# IR_module_V4.net
KiCad netlist of a schematic drawn in EAGLE
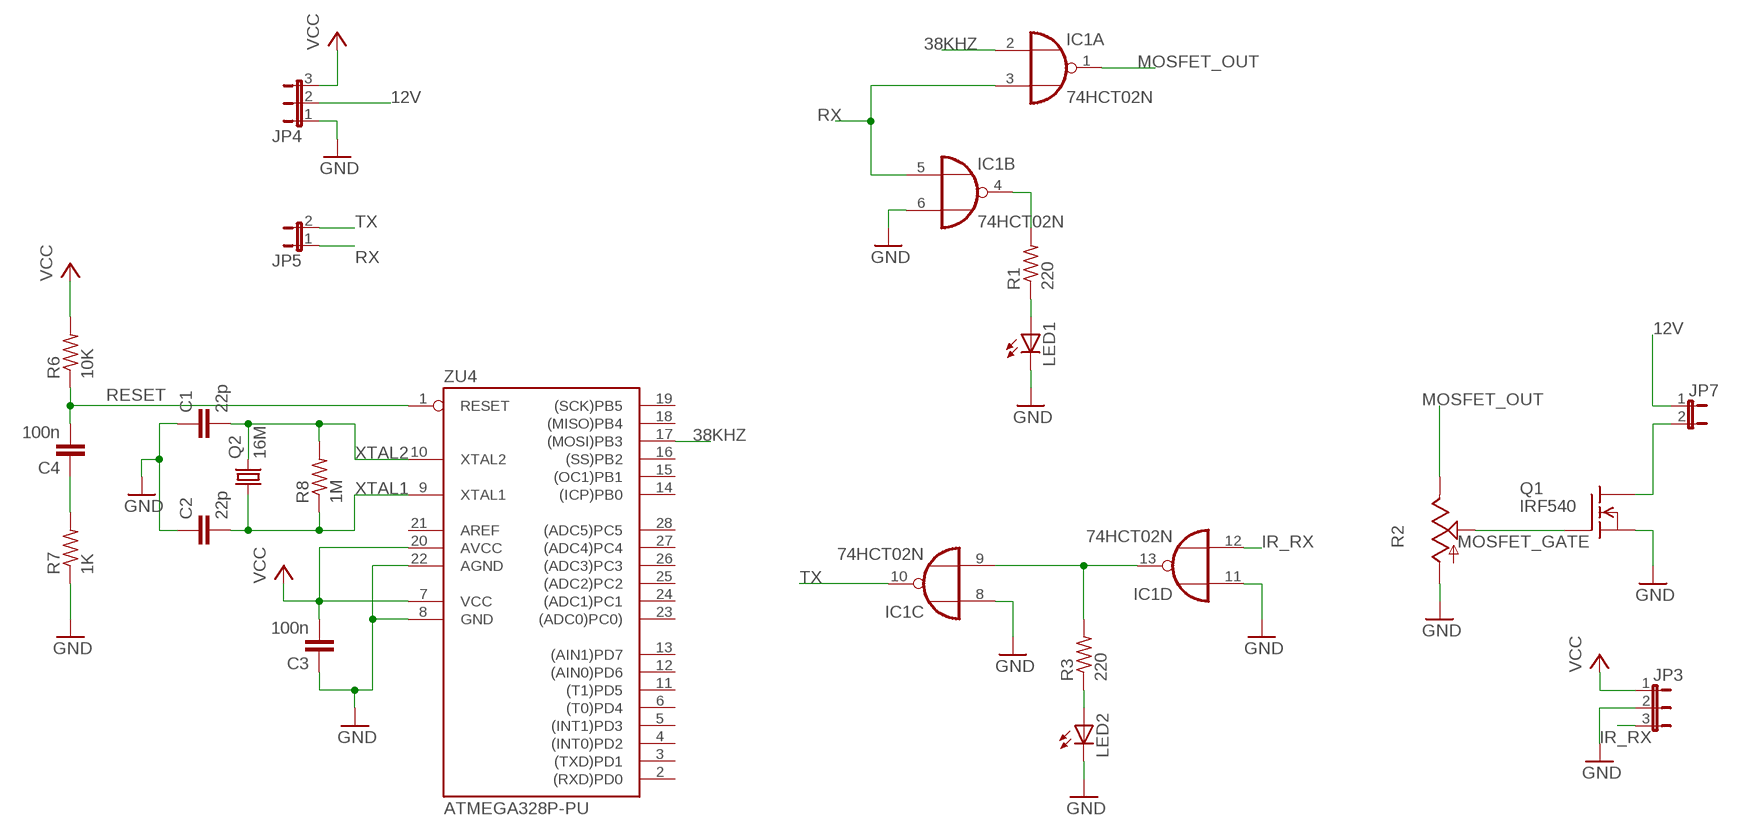
[diagram p0: schematic, sheet 1]

(export (version "E")
  (design (tool "Eeschema 10.0.6"))
  (components
    (comp (ref "C1")
      (value "22p")
      (footprint "eagle-import:CAP-PTH-SMALLEZ")
      (libsource (lib "eagle-import") (part "CAPEZ"))
    )
    (comp (ref "C2")
      (value "22p")
      (footprint "eagle-import:CAP-PTH-SMALLEZ")
      (libsource (lib "eagle-import") (part "CAPEZ"))
    )
    (comp (ref "C3")
      (value "100n")
      (footprint "eagle-import:CAP-PTH-SMALLEZ")
      (libsource (lib "eagle-import") (part "CAPEZ"))
    )
    (comp (ref "C4")
      (value "100n")
      (footprint "eagle-import:CAP-PTH-SMALLEZ")
      (libsource (lib "eagle-import") (part "CAPEZ"))
    )
    (comp (ref "IC1")
      (value "74HCT02N")
      (footprint "eagle-import:DIL14")
      (libsource (lib "eagle-import") (part "7402NHCT"))
    )
    (comp (ref "JP3")
      (value "JP2E")
      (footprint "eagle-import:JP2")
      (libsource (lib "eagle-import") (part "JP2E"))
    )
    (comp (ref "JP4")
      (value "JP2E")
      (footprint "eagle-import:JP2")
      (libsource (lib "eagle-import") (part "JP2E"))
    )
    (comp (ref "JP5")
      (value "JP1E")
      (footprint "eagle-import:JP1")
      (libsource (lib "eagle-import") (part "JP1E"))
    )
    (comp (ref "JP7")
      (value "JP1E")
      (footprint "eagle-import:JP1")
      (libsource (lib "eagle-import") (part "JP1E"))
    )
    (comp (ref "LED1")
      (value "LED5MM")
      (footprint "eagle-import:LED5MM")
      (libsource (lib "eagle-import") (part "LED5MM"))
    )
    (comp (ref "LED2")
      (value "LED5MM")
      (footprint "eagle-import:LED5MM")
      (libsource (lib "eagle-import") (part "LED5MM"))
    )
    (comp (ref "Q1")
      (value "IRF540")
      (footprint "eagle-import:TO220")
      (libsource (lib "eagle-import") (part "IRF540"))
    )
    (comp (ref "Q2")
      (value "16M")
      (footprint "eagle-import:HC49_S")
      (libsource (lib "eagle-import") (part "CRYSTALHC49S"))
    )
    (comp (ref "R1")
      (value "220")
      (footprint "eagle-import:0207_10")
      (libsource (lib "eagle-import") (part "R-US_0207/10"))
    )
    (comp (ref "R2")
      (value "TRIM_US-B25P")
      (footprint "eagle-import:B25P")
      (libsource (lib "eagle-import") (part "TRIM_US-B25P"))
    )
    (comp (ref "R3")
      (value "220")
      (footprint "eagle-import:0207_10")
      (libsource (lib "eagle-import") (part "R-US_0207/10"))
    )
    (comp (ref "R6")
      (value "10K")
      (footprint "eagle-import:0207_10")
      (libsource (lib "eagle-import") (part "R-US_0207/10"))
    )
    (comp (ref "R7")
      (value "1K")
      (footprint "eagle-import:0207_10")
      (libsource (lib "eagle-import") (part "R-US_0207/10"))
    )
    (comp (ref "R8")
      (value "1M")
      (footprint "eagle-import:0207_10")
      (libsource (lib "eagle-import") (part "R-US_0207/10"))
    )
    (comp (ref "ZU4")
      (value "ATMEGA328P-PU")
      (footprint "eagle-import:DIL28-3")
      (libsource (lib "eagle-import") (part "ATMEGA328P-PU"))
    )
  )
  (nets
    (net (code "1") (name "/12V") (class "Default")
      (node (ref "JP4") (pin "2") (pinfunction "2_2") (pintype "passive"))
      (node (ref "JP7") (pin "1") (pinfunction "1_1") (pintype "passive"))
    )
    (net (code "2") (name "/38KHZ") (class "Default")
      (node (ref "IC1") (pin "2") (pinfunction "I0_2") (pintype "input"))
      (node (ref "ZU4") (pin "17") (pinfunction "(MOSI)PB3_17") (pintype "bidirectional"))
    )
    (net (code "3") (name "/IR_RX") (class "Default")
      (node (ref "IC1") (pin "12") (pinfunction "I1_12") (pintype "input"))
      (node (ref "JP3") (pin "3") (pinfunction "3_3") (pintype "passive"))
    )
    (net (code "4") (name "/MOSFET_GATE") (class "Default")
      (node (ref "Q1") (pin "1") (pinfunction "G_1") (pintype "passive"))
      (node (ref "R2") (pin "S") (pinfunction "S_S") (pintype "passive"))
    )
    (net (code "5") (name "/MOSFET_OUT") (class "Default")
      (node (ref "IC1") (pin "1") (pinfunction "O_1") (pintype "output"))
      (node (ref "R2") (pin "E") (pinfunction "E_E") (pintype "passive"))
    )
    (net (code "6") (name "/RESET") (class "Default")
      (node (ref "C4") (pin "2") (pinfunction "2_2") (pintype "passive"))
      (node (ref "R6") (pin "1") (pinfunction "1_1") (pintype "passive"))
      (node (ref "ZU4") (pin "1") (pinfunction "RESET_1") (pintype "input"))
    )
    (net (code "7") (name "/RX") (class "Default")
      (node (ref "IC1") (pin "3") (pinfunction "I1_3") (pintype "input"))
      (node (ref "IC1") (pin "5") (pinfunction "I0_5") (pintype "input"))
      (node (ref "JP5") (pin "1") (pinfunction "1_1") (pintype "passive"))
    )
    (net (code "8") (name "/TX") (class "Default")
      (node (ref "IC1") (pin "10") (pinfunction "O_10") (pintype "output"))
      (node (ref "JP5") (pin "2") (pinfunction "2_2") (pintype "passive"))
    )
    (net (code "9") (name "/XTAL1") (class "Default")
      (node (ref "C2") (pin "2") (pinfunction "2_2") (pintype "passive"))
      (node (ref "Q2") (pin "1") (pinfunction "1_1") (pintype "passive"))
      (node (ref "R8") (pin "1") (pinfunction "1_1") (pintype "passive"))
      (node (ref "ZU4") (pin "9") (pinfunction "XTAL1_9") (pintype "bidirectional"))
    )
    (net (code "10") (name "/XTAL2") (class "Default")
      (node (ref "C1") (pin "2") (pinfunction "2_2") (pintype "passive"))
      (node (ref "Q2") (pin "2") (pinfunction "2_2") (pintype "passive"))
      (node (ref "R8") (pin "2") (pinfunction "2_2") (pintype "passive"))
      (node (ref "ZU4") (pin "10") (pinfunction "XTAL2_10") (pintype "bidirectional"))
    )
    (net (code "11") (name "GND") (class "Default")
      (node (ref "C1") (pin "1") (pinfunction "1_1") (pintype "passive"))
      (node (ref "C2") (pin "1") (pinfunction "1_1") (pintype "passive"))
      (node (ref "C3") (pin "1") (pinfunction "1_1") (pintype "passive"))
      (node (ref "IC1") (pin "11") (pinfunction "I0_11") (pintype "input"))
      (node (ref "IC1") (pin "6") (pinfunction "I1_6") (pintype "input"))
      (node (ref "IC1") (pin "8") (pinfunction "I0_8") (pintype "input"))
      (node (ref "JP3") (pin "2") (pinfunction "2_2") (pintype "passive"))
      (node (ref "JP4") (pin "1") (pinfunction "1_1") (pintype "passive"))
      (node (ref "LED1") (pin "K") (pinfunction "C_K") (pintype "passive"))
      (node (ref "LED2") (pin "K") (pinfunction "C_K") (pintype "passive"))
      (node (ref "Q1") (pin "3") (pinfunction "S_3") (pintype "passive"))
      (node (ref "R2") (pin "A") (pinfunction "A_A") (pintype "passive"))
      (node (ref "R7") (pin "1") (pinfunction "1_1") (pintype "passive"))
      (node (ref "ZU4") (pin "22") (pinfunction "AGND_22") (pintype "power_in"))
      (node (ref "ZU4") (pin "8") (pinfunction "GND_8") (pintype "power_in"))
    )
    (net (code "12") (name "Net-(C4-Pad1)") (class "Default")
      (node (ref "C4") (pin "1") (pinfunction "1_1") (pintype "passive"))
      (node (ref "R7") (pin "2") (pinfunction "2_2") (pintype "passive"))
    )
    (net (code "13") (name "Net-(IC1B-O)") (class "Default")
      (node (ref "IC1") (pin "4") (pinfunction "O_4") (pintype "output"))
      (node (ref "R1") (pin "2") (pinfunction "2_2") (pintype "passive"))
    )
    (net (code "14") (name "Net-(IC1C-I1)") (class "Default")
      (node (ref "IC1") (pin "13") (pinfunction "O_13") (pintype "output"))
      (node (ref "IC1") (pin "9") (pinfunction "I1_9") (pintype "input"))
      (node (ref "R3") (pin "2") (pinfunction "2_2") (pintype "passive"))
    )
    (net (code "15") (name "Net-(LED1-PadA)") (class "Default")
      (node (ref "LED1") (pin "A") (pinfunction "A_A") (pintype "passive"))
      (node (ref "R1") (pin "1") (pinfunction "1_1") (pintype "passive"))
    )
    (net (code "16") (name "Net-(LED2-PadA)") (class "Default")
      (node (ref "LED2") (pin "A") (pinfunction "A_A") (pintype "passive"))
      (node (ref "R3") (pin "1") (pinfunction "1_1") (pintype "passive"))
    )
    (net (code "17") (name "Net-(Q1-D)") (class "Default")
      (node (ref "JP7") (pin "2") (pinfunction "2_2") (pintype "passive"))
      (node (ref "Q1") (pin "2") (pinfunction "D_2") (pintype "passive"))
    )
    (net (code "18") (name "VCC") (class "Default")
      (node (ref "C3") (pin "2") (pinfunction "2_2") (pintype "passive"))
      (node (ref "JP3") (pin "1") (pinfunction "1_1") (pintype "passive"))
      (node (ref "JP4") (pin "3") (pinfunction "3_3") (pintype "passive"))
      (node (ref "R6") (pin "2") (pinfunction "2_2") (pintype "passive"))
      (node (ref "ZU4") (pin "20") (pinfunction "AVCC_20") (pintype "power_in"))
      (node (ref "ZU4") (pin "7") (pinfunction "VCC_7") (pintype "power_in"))
    )
    (net (code "19") (name "unconnected-(ZU4-(ADC0)PC0)-Pad23)") (class "Default")
      (node (ref "ZU4") (pin "23") (pinfunction "(ADC0)PC0)_23") (pintype "bidirectional"))
    )
    (net (code "20") (name "unconnected-(ZU4-(ADC1)PC1-Pad24)") (class "Default")
      (node (ref "ZU4") (pin "24") (pinfunction "(ADC1)PC1_24") (pintype "bidirectional"))
    )
    (net (code "21") (name "unconnected-(ZU4-(ADC2)PC2-Pad25)") (class "Default")
      (node (ref "ZU4") (pin "25") (pinfunction "(ADC2)PC2_25") (pintype "bidirectional"))
    )
    (net (code "22") (name "unconnected-(ZU4-(ADC3)PC3-Pad26)") (class "Default")
      (node (ref "ZU4") (pin "26") (pinfunction "(ADC3)PC3_26") (pintype "bidirectional"))
    )
    (net (code "23") (name "unconnected-(ZU4-(ADC4)PC4-Pad27)") (class "Default")
      (node (ref "ZU4") (pin "27") (pinfunction "(ADC4)PC4_27") (pintype "bidirectional"))
    )
    (net (code "24") (name "unconnected-(ZU4-(ADC5)PC5-Pad28)") (class "Default")
      (node (ref "ZU4") (pin "28") (pinfunction "(ADC5)PC5_28") (pintype "bidirectional"))
    )
    (net (code "25") (name "unconnected-(ZU4-(AIN0)PD6-Pad12)") (class "Default")
      (node (ref "ZU4") (pin "12") (pinfunction "(AIN0)PD6_12") (pintype "bidirectional"))
    )
    (net (code "26") (name "unconnected-(ZU4-(AIN1)PD7-Pad13)") (class "Default")
      (node (ref "ZU4") (pin "13") (pinfunction "(AIN1)PD7_13") (pintype "bidirectional"))
    )
    (net (code "27") (name "unconnected-(ZU4-(ICP)PB0-Pad14)") (class "Default")
      (node (ref "ZU4") (pin "14") (pinfunction "(ICP)PB0_14") (pintype "bidirectional"))
    )
    (net (code "28") (name "unconnected-(ZU4-(INT0)PD2-Pad4)") (class "Default")
      (node (ref "ZU4") (pin "4") (pinfunction "(INT0)PD2_4") (pintype "bidirectional"))
    )
    (net (code "29") (name "unconnected-(ZU4-(INT1)PD3-Pad5)") (class "Default")
      (node (ref "ZU4") (pin "5") (pinfunction "(INT1)PD3_5") (pintype "bidirectional"))
    )
    (net (code "30") (name "unconnected-(ZU4-(MISO)PB4-Pad18)") (class "Default")
      (node (ref "ZU4") (pin "18") (pinfunction "(MISO)PB4_18") (pintype "bidirectional"))
    )
    (net (code "31") (name "unconnected-(ZU4-(OC1)PB1-Pad15)") (class "Default")
      (node (ref "ZU4") (pin "15") (pinfunction "(OC1)PB1_15") (pintype "bidirectional"))
    )
    (net (code "32") (name "unconnected-(ZU4-(RXD)PD0-Pad2)") (class "Default")
      (node (ref "ZU4") (pin "2") (pinfunction "(RXD)PD0_2") (pintype "bidirectional"))
    )
    (net (code "33") (name "unconnected-(ZU4-(SCK)PB5-Pad19)") (class "Default")
      (node (ref "ZU4") (pin "19") (pinfunction "(SCK)PB5_19") (pintype "bidirectional"))
    )
    (net (code "34") (name "unconnected-(ZU4-(SS)PB2-Pad16)") (class "Default")
      (node (ref "ZU4") (pin "16") (pinfunction "(SS)PB2_16") (pintype "bidirectional"))
    )
    (net (code "35") (name "unconnected-(ZU4-(T0)PD4-Pad6)") (class "Default")
      (node (ref "ZU4") (pin "6") (pinfunction "(T0)PD4_6") (pintype "bidirectional"))
    )
    (net (code "36") (name "unconnected-(ZU4-(T1)PD5-Pad11)") (class "Default")
      (node (ref "ZU4") (pin "11") (pinfunction "(T1)PD5_11") (pintype "bidirectional"))
    )
    (net (code "37") (name "unconnected-(ZU4-(TXD)PD1-Pad3)") (class "Default")
      (node (ref "ZU4") (pin "3") (pinfunction "(TXD)PD1_3") (pintype "bidirectional"))
    )
    (net (code "38") (name "unconnected-(ZU4-AREF-Pad21)") (class "Default")
      (node (ref "ZU4") (pin "21") (pinfunction "AREF_21") (pintype "passive"))
    )
  )
)
